# button1.net
KiCad netlist of a schematic drawn in EAGLE
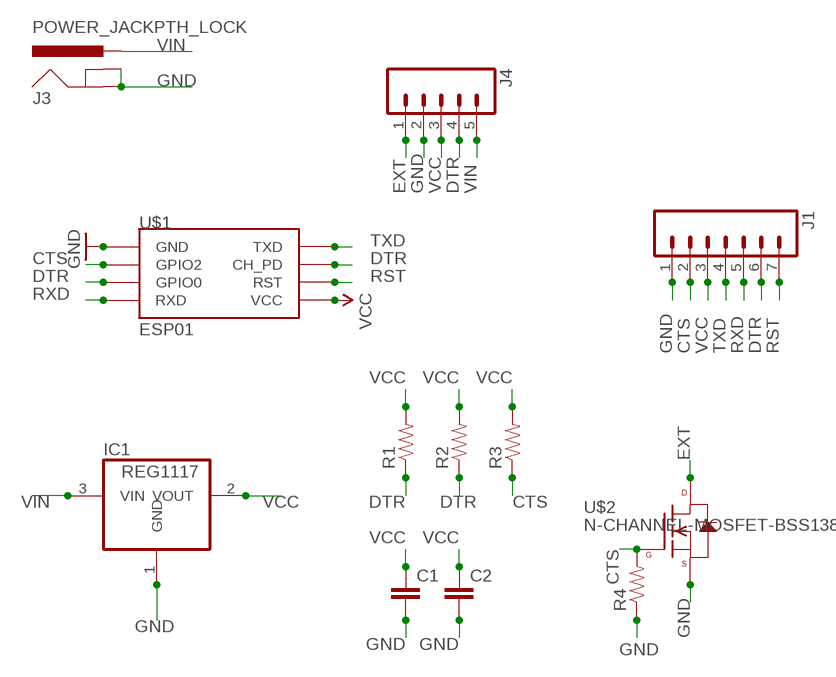
[diagram p0: schematic, sheet 1]

(export (version "E")
  (design (tool "Eeschema 10.0.6"))
  (components
    (comp (ref "C1")
      (value "CAP0603-CAP")
      (footprint "eagle-import:0603-CAP")
      (libsource (lib "eagle-import") (part "CAP0603-CAP"))
    )
    (comp (ref "C2")
      (value "CAP0603-CAP")
      (footprint "eagle-import:0603-CAP")
      (libsource (lib "eagle-import") (part "CAP0603-CAP"))
    )
    (comp (ref "IC1")
      (value "REG1117")
      (footprint "eagle-import:SOT223")
      (libsource (lib "eagle-import") (part "REG1117"))
    )
    (comp (ref "J1")
      (value "M07LOCK_LONGPADS")
      (footprint "eagle-import:1X07_LOCK_LONGPADS")
      (libsource (lib "eagle-import") (part "M07LOCK_LONGPADS"))
    )
    (comp (ref "J3")
      (value "POWER_JACKPTH_LOCK")
      (footprint "eagle-import:POWER_JACK_PTH_LOCK")
      (libsource (lib "eagle-import") (part "POWER_JACKPTH_LOCK"))
    )
    (comp (ref "J4")
      (value "M05LOCK_LONGPADS")
      (footprint "eagle-import:1X05_LOCK_LONGPADS")
      (libsource (lib "eagle-import") (part "M05LOCK_LONGPADS"))
    )
    (comp (ref "R1")
      (value "RESISTOR0603")
      (footprint "eagle-import:0603-RES")
      (libsource (lib "eagle-import") (part "RESISTOR0603"))
    )
    (comp (ref "R2")
      (value "RESISTOR0603")
      (footprint "eagle-import:0603-RES")
      (libsource (lib "eagle-import") (part "RESISTOR0603"))
    )
    (comp (ref "R3")
      (value "RESISTOR0603")
      (footprint "eagle-import:0603-RES")
      (libsource (lib "eagle-import") (part "RESISTOR0603"))
    )
    (comp (ref "R4")
      (value "RESISTOR0603")
      (footprint "eagle-import:0603-RES")
      (libsource (lib "eagle-import") (part "RESISTOR0603"))
    )
    (comp (ref "U$1")
      (value "ESP01")
      (footprint "eagle-import:ESP01")
      (libsource (lib "eagle-import") (part "ESP01"))
    )
    (comp (ref "U$2")
      (value "N-CHANNEL-MOSFET-BSS138")
      (footprint "eagle-import:SOT23-3")
      (libsource (lib "eagle-import") (part "N-CHANNEL-MOSFET-BSS138"))
    )
  )
  (nets
    (net (code "1") (name "/CTS") (class "Default")
      (node (ref "J1") (pin "2") (pinfunction "2_2") (pintype "passive"))
      (node (ref "R3") (pin "1") (pinfunction "1_1") (pintype "passive"))
      (node (ref "R4") (pin "2") (pinfunction "2_2") (pintype "passive"))
      (node (ref "U$1") (pin "GPIO2") (pinfunction "GPIO2_GPIO2") (pintype "bidirectional"))
      (node (ref "U$2") (pin "1") (pinfunction "G_1") (pintype "passive"))
    )
    (net (code "2") (name "/DTR") (class "Default")
      (node (ref "J1") (pin "6") (pinfunction "6_6") (pintype "passive"))
      (node (ref "J4") (pin "4") (pinfunction "4_4") (pintype "passive"))
      (node (ref "R1") (pin "1") (pinfunction "1_1") (pintype "passive"))
      (node (ref "R2") (pin "1") (pinfunction "1_1") (pintype "passive"))
      (node (ref "U$1") (pin "CH_PD") (pinfunction "CH_PD_CH_PD") (pintype "bidirectional"))
      (node (ref "U$1") (pin "GPIO0") (pinfunction "GPIO0_GPIO0") (pintype "bidirectional"))
    )
    (net (code "3") (name "/EXT") (class "Default")
      (node (ref "J4") (pin "1") (pinfunction "1_1") (pintype "passive"))
      (node (ref "U$2") (pin "3") (pinfunction "D_3") (pintype "passive"))
    )
    (net (code "4") (name "/RST") (class "Default")
      (node (ref "J1") (pin "7") (pinfunction "7_7") (pintype "passive"))
      (node (ref "U$1") (pin "RST") (pinfunction "RST_RST") (pintype "bidirectional"))
    )
    (net (code "5") (name "/RXD") (class "Default")
      (node (ref "J1") (pin "5") (pinfunction "5_5") (pintype "passive"))
      (node (ref "U$1") (pin "RX") (pinfunction "RXD_RX") (pintype "bidirectional"))
    )
    (net (code "6") (name "/TXD") (class "Default")
      (node (ref "J1") (pin "4") (pinfunction "4_4") (pintype "passive"))
      (node (ref "U$1") (pin "TX") (pinfunction "TXD_TX") (pintype "bidirectional"))
    )
    (net (code "7") (name "/VIN") (class "Default")
      (node (ref "IC1") (pin "3") (pinfunction "VIN_3") (pintype "input"))
      (node (ref "J3") (pin "PWR") (pinfunction "PWR_PWR") (pintype "bidirectional"))
      (node (ref "J4") (pin "5") (pinfunction "5_5") (pintype "passive"))
    )
    (net (code "8") (name "GND") (class "Default")
      (node (ref "C1") (pin "2") (pinfunction "2_2") (pintype "passive"))
      (node (ref "C2") (pin "2") (pinfunction "2_2") (pintype "passive"))
      (node (ref "IC1") (pin "1") (pinfunction "GND_1") (pintype "power_in"))
      (node (ref "J1") (pin "1") (pinfunction "1_1") (pintype "passive"))
      (node (ref "J3") (pin "GND") (pinfunction "GND_GND") (pintype "bidirectional"))
      (node (ref "J3") (pin "GNDBREAK") (pinfunction "GNDBREAK_GNDBREAK") (pintype "bidirectional"))
      (node (ref "J4") (pin "2") (pinfunction "2_2") (pintype "passive"))
      (node (ref "R4") (pin "1") (pinfunction "1_1") (pintype "passive"))
      (node (ref "U$1") (pin "GND") (pinfunction "GND_GND") (pintype "bidirectional"))
      (node (ref "U$2") (pin "2") (pinfunction "S_2") (pintype "passive"))
    )
    (net (code "9") (name "VCC") (class "Default")
      (node (ref "C1") (pin "1") (pinfunction "1_1") (pintype "passive"))
      (node (ref "C2") (pin "1") (pinfunction "1_1") (pintype "passive"))
      (node (ref "IC1") (pin "2") (pinfunction "VOUT_2") (pintype "output"))
      (node (ref "J1") (pin "3") (pinfunction "3_3") (pintype "passive"))
      (node (ref "J4") (pin "3") (pinfunction "3_3") (pintype "passive"))
      (node (ref "R1") (pin "2") (pinfunction "2_2") (pintype "passive"))
      (node (ref "R2") (pin "2") (pinfunction "2_2") (pintype "passive"))
      (node (ref "R3") (pin "2") (pinfunction "2_2") (pintype "passive"))
      (node (ref "U$1") (pin "VCC") (pinfunction "VCC_VCC") (pintype "bidirectional"))
    )
  )
)
